# DC_SIGNAL_FILTER.net
KiCad netlist of a schematic drawn in Altium Designer
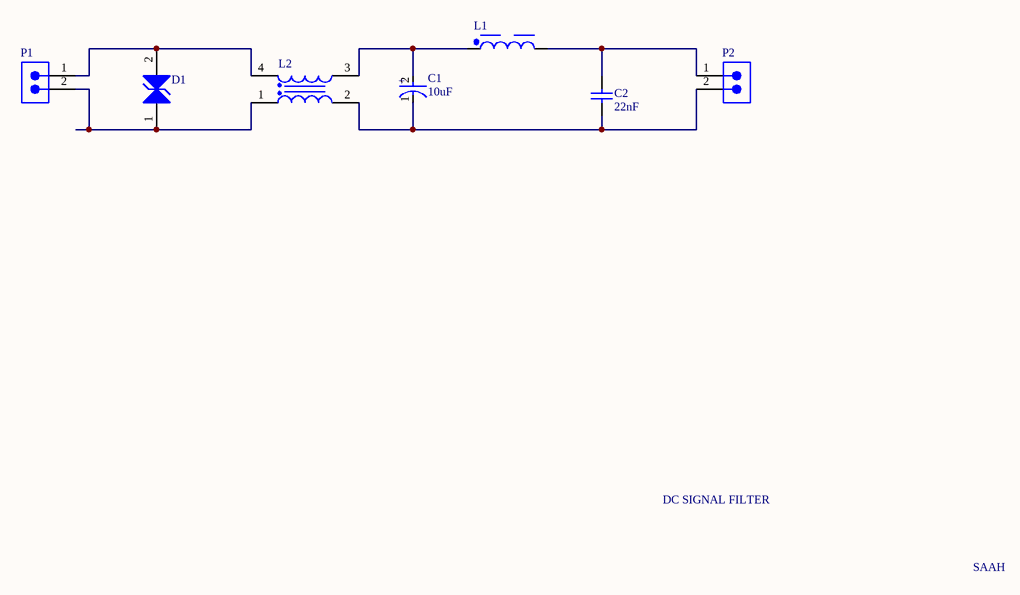
[diagram p0: DC_SIGNAL_FILTER.SchDoc]

(export (version "E")
  (design (tool "Eeschema 10.0.6"))
  (components
    (comp (ref "C1")
      (value "10uF")
      (footprint "FP-HDF-MFG")
      (description "CAP ALUM 10UF 20% 100V SMD")
      (fields (field (name "VOLTAGE") "100V") (field (name "TOLERANCE") "20%"))
      (libsource (lib "Altium Content Vault") (part "cf48714ba7e38822c1575c7ec0b6d1f"))
    )
    (comp (ref "C2")
      (value "22nF")
      (footprint "WCAP-FTXX_L13W4.5H9.5_CS")
      (description "890334023011CS WCAP-FTXX Film Capacitor 22nF 310Vac")
      (fields (field (name "TOLERANCE") "10%"))
      (libsource (lib "Altium Content Vault") (part "Capacitor_Non-Polarized"))
    )
    (comp (ref "D1")
      (value "824501500")
      (footprint "WE-TVSP_DO-214AC_Bidirectional")
      (description "824501500 WE-TVSP Power TVS Diode")
      (libsource (lib "Altium Content Vault") (part "WE-TVSP_Bidirectional"))
    )
    (comp (ref "L1")
      (value "768775282")
      (footprint "WE-PD2 HV_7850")
      (fields (field (name "TOLERANCE") "10%"))
      (libsource (lib "Altium Content Vault") (part "Inductor - 2"))
    )
    (comp (ref "L2")
      (value "744235251")
      (footprint "WE-CNSW_1812")
      (description "CMC 250UH 200MA 2LN SMD AEC-Q200")
      (fields (field (name "TOLERANCE") "25%"))
      (libsource (lib "Altium Content Vault") (part "WE-CNSW"))
    )
    (comp (ref "P1")
      (value "653102124022")
      (footprint "653102124022")
      (libsource (lib "Altium Content Vault") (part "Header_Male_1R_02P"))
    )
    (comp (ref "P2")
      (value "653102124022")
      (footprint "653102124022")
      (libsource (lib "Altium Content Vault") (part "Header_Male_1R_02P"))
    )
  )
  (nets
    (net (code "1") (name "Net-(C1-A)") (class "Default")
      (node (ref "C1") (pin "2") (pinfunction "A_2") (pintype "passive"))
      (node (ref "L1") (pin "1") (pinfunction "1_1") (pintype "passive"))
      (node (ref "L2") (pin "3") (pinfunction "3_3") (pintype "passive"))
    )
    (net (code "2") (name "Net-(C1-C)") (class "Default")
      (node (ref "C1") (pin "1") (pinfunction "C_1") (pintype "passive"))
      (node (ref "C2") (pin "1") (pinfunction "1_1") (pintype "passive"))
      (node (ref "L2") (pin "2") (pinfunction "2_2") (pintype "passive"))
      (node (ref "P2") (pin "2") (pinfunction "2_2") (pintype "passive"))
    )
    (net (code "3") (name "Net-(C2-Pad2)") (class "Default")
      (node (ref "C2") (pin "2") (pinfunction "2_2") (pintype "passive"))
      (node (ref "L1") (pin "2") (pinfunction "2_2") (pintype "passive"))
      (node (ref "P2") (pin "1") (pinfunction "1_1") (pintype "passive"))
    )
    (net (code "4") (name "Net-(D1-Pad1)") (class "Default")
      (node (ref "D1") (pin "1") (pinfunction "1_1") (pintype "passive"))
      (node (ref "L2") (pin "1") (pinfunction "1_1") (pintype "passive"))
      (node (ref "P1") (pin "2") (pinfunction "2_2") (pintype "passive"))
    )
    (net (code "5") (name "Net-(D1-Pad2)") (class "Default")
      (node (ref "D1") (pin "2") (pinfunction "2_2") (pintype "passive"))
      (node (ref "L2") (pin "4") (pinfunction "4_4") (pintype "passive"))
      (node (ref "P1") (pin "1") (pinfunction "1_1") (pintype "passive"))
    )
  )
)
